# TeamG_PCB.net
KiCad netlist of a schematic drawn in EAGLE
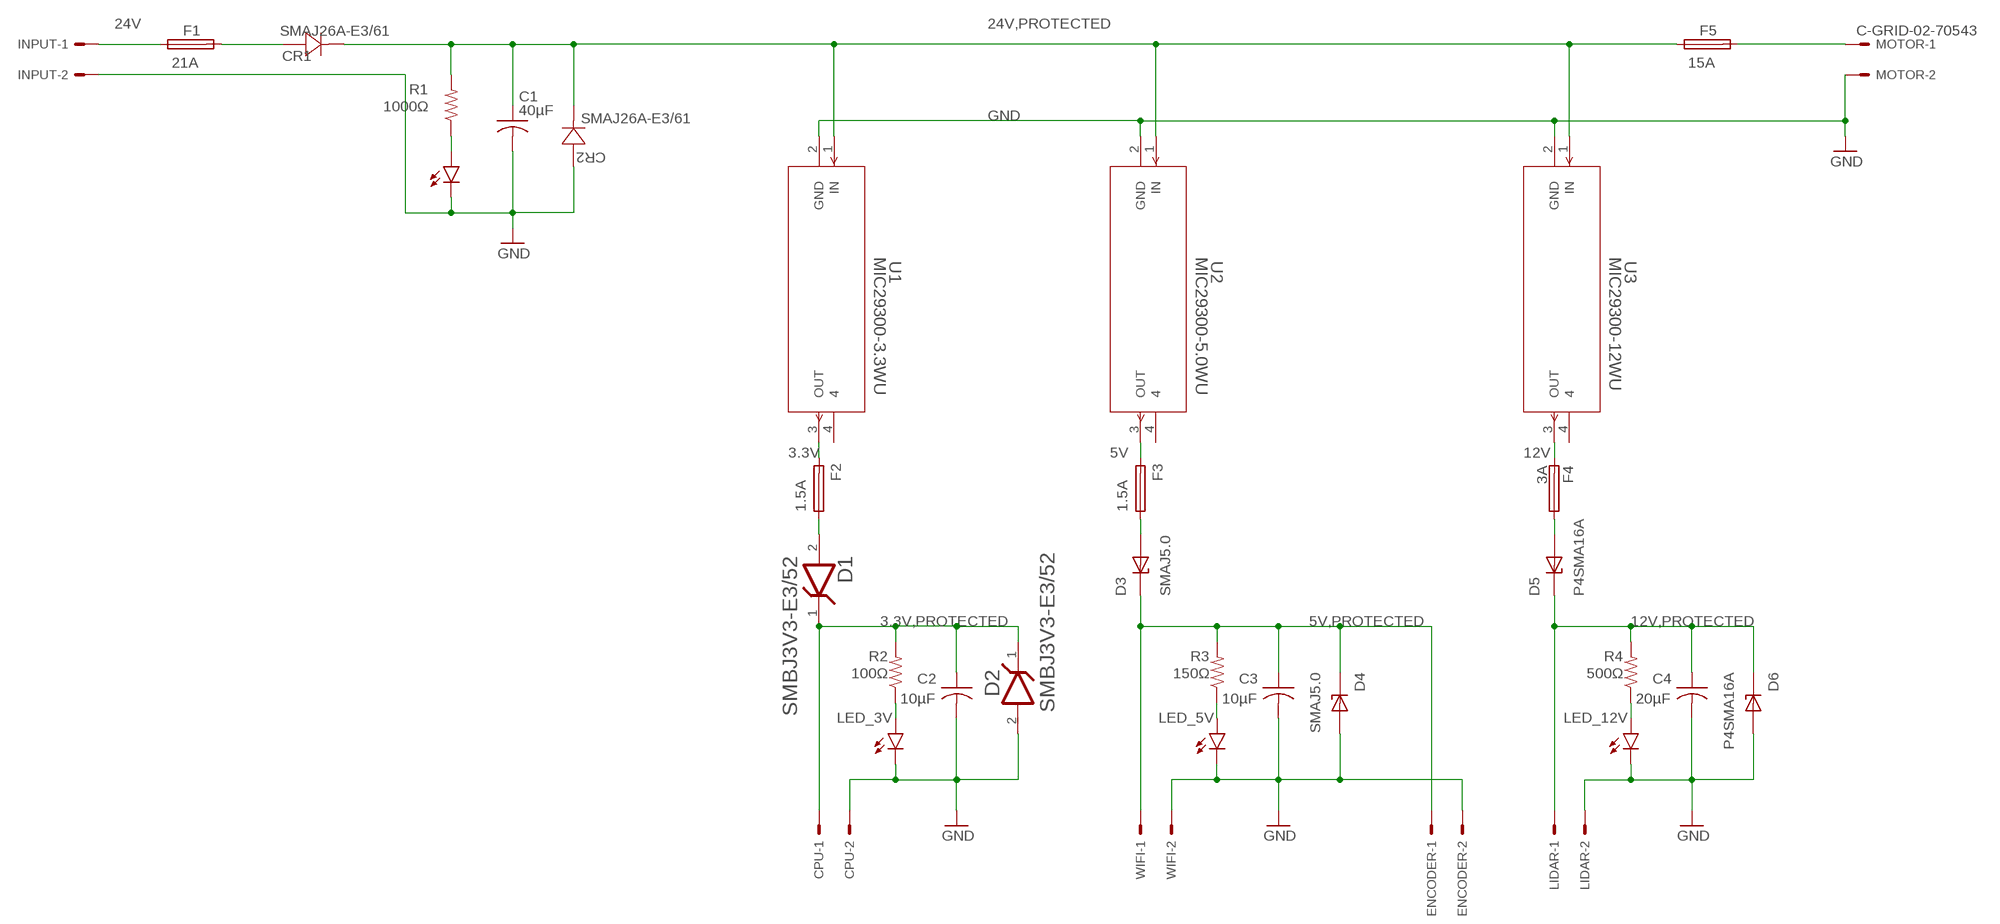
[diagram p0: schematic, sheet 1]

(export (version "E")
  (design (tool "Eeschema 10.0.6"))
  (components
    (comp (ref "24VLED")
      (value "0")
      (footprint "eagle-import:1206")
      (libsource (lib "eagle-import") (part "LEDSMT1206"))
    )
    (comp (ref "C1")
      (value "40µF")
      (footprint "eagle-import:C1210")
      (libsource (lib "eagle-import") (part "C-USC1210"))
    )
    (comp (ref "C2")
      (value "10µF")
      (footprint "eagle-import:C1210")
      (libsource (lib "eagle-import") (part "C-USC1210"))
    )
    (comp (ref "C3")
      (value "10µF")
      (footprint "eagle-import:C1210")
      (libsource (lib "eagle-import") (part "C-USC1210"))
    )
    (comp (ref "C4")
      (value "20µF")
      (footprint "eagle-import:C1210")
      (libsource (lib "eagle-import") (part "C-USC1210"))
    )
    (comp (ref "CPU")
      (value "C-GRID-02-70543")
      (footprint "eagle-import:70543-02")
      (fields (field (name "MF") "MOLEX"))
      (libsource (lib "eagle-import") (part "C-GRID-02-70543"))
    )
    (comp (ref "CR1")
      (value "SMAJ26A-E3/61")
      (footprint "eagle-import:DIODE_DO-214AC")
      (fields (field (name "COPYRIGHT") "Copyright (C) 2022 Ultra Librarian. All rights reserved."))
      (libsource (lib "eagle-import") (part "SMAJ26A-E3/61"))
    )
    (comp (ref "CR2")
      (value "SMAJ26A-E3/61")
      (footprint "eagle-import:DIODE_DO-214AC")
      (fields (field (name "COPYRIGHT") "Copyright (C) 2022 Ultra Librarian. All rights reserved."))
      (libsource (lib "eagle-import") (part "SMAJ26A-E3/61"))
    )
    (comp (ref "D1")
      (value "VISHAY_SMBJ3V3-E3-52VISHAY_SMBJ3V3-E3-52_0_0")
      (footprint "eagle-import:VISHAY_SMBJ3V3-E3-52_0")
      (fields
        (field (name "DIGIKEY_PART_NUMBER") "SMBJ3V3-E3/52GICT-ND")
        (field (name "MF") "Vishay")
        (field (name "MOUSER_PART_NUMBER") "625-SMBJ3V3-E3")
      )
      (libsource (lib "eagle-import") (part "VISHAY_SMBJ3V3-E3-52VISHAY_SMBJ3V3-E3-52_0_0"))
    )
    (comp (ref "D2")
      (value "VISHAY_SMBJ3V3-E3-52VISHAY_SMBJ3V3-E3-52_0_0")
      (footprint "eagle-import:VISHAY_SMBJ3V3-E3-52_0")
      (fields
        (field (name "DIGIKEY_PART_NUMBER") "SMBJ3V3-E3/52GICT-ND")
        (field (name "MF") "Vishay")
        (field (name "MOUSER_PART_NUMBER") "625-SMBJ3V3-E3")
      )
      (libsource (lib "eagle-import") (part "VISHAY_SMBJ3V3-E3-52VISHAY_SMBJ3V3-E3-52_0_0"))
    )
    (comp (ref "D3")
      (value "SMAJ5.0")
      (footprint "eagle-import:DIOM4325X250N")
      (fields (field (name "MF") "Taiwan Semiconductor"))
      (libsource (lib "eagle-import") (part "SMAJ5.0"))
    )
    (comp (ref "D4")
      (value "SMAJ5.0")
      (footprint "eagle-import:DIOM4325X250N")
      (fields (field (name "MF") "Taiwan Semiconductor"))
      (libsource (lib "eagle-import") (part "SMAJ5.0"))
    )
    (comp (ref "D5")
      (value "P4SMA16A")
      (footprint "eagle-import:DIOM4325X250N")
      (fields (field (name "MF") "Taiwan Semiconductor"))
      (libsource (lib "eagle-import") (part "P4SMA16A"))
    )
    (comp (ref "D6")
      (value "P4SMA16A")
      (footprint "eagle-import:DIOM4325X250N")
      (fields (field (name "MF") "Taiwan Semiconductor"))
      (libsource (lib "eagle-import") (part "P4SMA16A"))
    )
    (comp (ref "ENCODER")
      (value "C-GRID-02-70543")
      (footprint "eagle-import:70543-02")
      (fields (field (name "MF") "MOLEX"))
      (libsource (lib "eagle-import") (part "C-GRID-02-70543"))
    )
    (comp (ref "F1")
      (value "21A")
      (footprint "eagle-import:TE5")
      (libsource (lib "eagle-import") (part "TE5"))
    )
    (comp (ref "F2")
      (value "1.5A")
      (footprint "eagle-import:TE5")
      (libsource (lib "eagle-import") (part "TE5"))
    )
    (comp (ref "F3")
      (value "1.5A")
      (footprint "eagle-import:TE5")
      (libsource (lib "eagle-import") (part "TE5"))
    )
    (comp (ref "F4")
      (value "3A")
      (footprint "eagle-import:TE5")
      (libsource (lib "eagle-import") (part "TE5"))
    )
    (comp (ref "F5")
      (value "15A")
      (footprint "eagle-import:TE5")
      (libsource (lib "eagle-import") (part "TE5"))
    )
    (comp (ref "INPUT")
      (value "5566-2")
      (footprint "eagle-import:5566-2")
      (libsource (lib "eagle-import") (part "5566-2"))
    )
    (comp (ref "LED_3V")
      (value "0")
      (footprint "eagle-import:1206")
      (libsource (lib "eagle-import") (part "LEDSMT1206"))
    )
    (comp (ref "LED_5V")
      (value "0")
      (footprint "eagle-import:1206")
      (libsource (lib "eagle-import") (part "LEDSMT1206"))
    )
    (comp (ref "LED_12V")
      (value "0")
      (footprint "eagle-import:1206")
      (libsource (lib "eagle-import") (part "LEDSMT1206"))
    )
    (comp (ref "LIDAR")
      (value "C-GRID-02-70543")
      (footprint "eagle-import:70543-02")
      (fields (field (name "MF") "MOLEX"))
      (libsource (lib "eagle-import") (part "C-GRID-02-70543"))
    )
    (comp (ref "MOTOR")
      (value "C-GRID-02-70543")
      (footprint "eagle-import:70543-02")
      (fields (field (name "MF") "MOLEX"))
      (libsource (lib "eagle-import") (part "C-GRID-02-70543"))
    )
    (comp (ref "R1")
      (value "1000Ω")
      (footprint "eagle-import:R1206")
      (libsource (lib "eagle-import") (part "R-US_R1206"))
    )
    (comp (ref "R2")
      (value "100Ω")
      (footprint "eagle-import:R1206")
      (libsource (lib "eagle-import") (part "R-US_R1206"))
    )
    (comp (ref "R3")
      (value "150Ω")
      (footprint "eagle-import:R1206")
      (libsource (lib "eagle-import") (part "R-US_R1206"))
    )
    (comp (ref "R4")
      (value "500Ω")
      (footprint "eagle-import:R1206")
      (libsource (lib "eagle-import") (part "R-US_R1206"))
    )
    (comp (ref "U1")
      (value "MIC29300-3.3WU")
      (footprint "eagle-import:TO-263-3_MCL")
      (fields (field (name "COPYRIGHT") "Copyright (C) 2022 Ultra Librarian. All rights reserved."))
      (libsource (lib "eagle-import") (part "MIC29300-3.3WU"))
    )
    (comp (ref "U2")
      (value "MIC29300-5.0WU")
      (footprint "eagle-import:TO-263-3_MCL")
      (fields (field (name "COPYRIGHT") "Copyright (C) 2022 Ultra Librarian. All rights reserved."))
      (libsource (lib "eagle-import") (part "MIC29300-5.0WU"))
    )
    (comp (ref "U3")
      (value "MIC29300-12WU")
      (footprint "eagle-import:TO-263-3_MCL")
      (fields (field (name "COPYRIGHT") "Copyright (C) 2022 Ultra Librarian. All rights reserved."))
      (libsource (lib "eagle-import") (part "MIC29300-12WU"))
    )
    (comp (ref "WIFI")
      (value "C-GRID-02-70543")
      (footprint "eagle-import:70543-02")
      (fields (field (name "MF") "MOLEX"))
      (libsource (lib "eagle-import") (part "C-GRID-02-70543"))
    )
  )
  (nets
    (net (code "1") (name "/3.3V") (class "Default")
      (node (ref "F2") (pin "2") (pinfunction "2_2") (pintype "passive"))
      (node (ref "U1") (pin "3") (pinfunction "OUT_3") (pintype "output"))
    )
    (net (code "2") (name "/3.3V,PROTECTED") (class "Default")
      (node (ref "C2") (pin "1") (pinfunction "1_1") (pintype "passive"))
      (node (ref "CPU") (pin "1") (pinfunction "S_1") (pintype "passive"))
      (node (ref "D1") (pin "1") (pinfunction "CATHODE_1") (pintype "passive"))
      (node (ref "D2") (pin "1") (pinfunction "CATHODE_1") (pintype "passive"))
      (node (ref "R2") (pin "2") (pinfunction "2_2") (pintype "passive"))
    )
    (net (code "3") (name "/5V") (class "Default")
      (node (ref "F3") (pin "2") (pinfunction "2_2") (pintype "passive"))
      (node (ref "U2") (pin "3") (pinfunction "OUT_3") (pintype "output"))
    )
    (net (code "4") (name "/5V,PROTECTED") (class "Default")
      (node (ref "C3") (pin "1") (pinfunction "1_1") (pintype "passive"))
      (node (ref "D3") (pin "C") (pinfunction "C_C") (pintype "passive"))
      (node (ref "D4") (pin "C") (pinfunction "C_C") (pintype "passive"))
      (node (ref "ENCODER") (pin "1") (pinfunction "S_1") (pintype "passive"))
      (node (ref "R3") (pin "2") (pinfunction "2_2") (pintype "passive"))
      (node (ref "WIFI") (pin "1") (pinfunction "S_1") (pintype "passive"))
    )
    (net (code "5") (name "/12V") (class "Default")
      (node (ref "F4") (pin "2") (pinfunction "2_2") (pintype "passive"))
      (node (ref "U3") (pin "3") (pinfunction "OUT_3") (pintype "output"))
    )
    (net (code "6") (name "/12V,PROTECTED") (class "Default")
      (node (ref "C4") (pin "1") (pinfunction "1_1") (pintype "passive"))
      (node (ref "D5") (pin "C") (pinfunction "C_C") (pintype "passive"))
      (node (ref "D6") (pin "C") (pinfunction "C_C") (pintype "passive"))
      (node (ref "LIDAR") (pin "1") (pinfunction "S_1") (pintype "passive"))
      (node (ref "R4") (pin "2") (pinfunction "2_2") (pintype "passive"))
    )
    (net (code "7") (name "/24V") (class "Default")
      (node (ref "F1") (pin "1") (pinfunction "1_1") (pintype "passive"))
      (node (ref "INPUT") (pin "1") (pinfunction "S_1") (pintype "passive"))
    )
    (net (code "8") (name "/24V,PROTECTED") (class "Default")
      (node (ref "C1") (pin "1") (pinfunction "1_1") (pintype "passive"))
      (node (ref "CR1") (pin "1") (pinfunction "1_1") (pintype "passive"))
      (node (ref "CR2") (pin "1") (pinfunction "1_1") (pintype "passive"))
      (node (ref "F5") (pin "1") (pinfunction "1_1") (pintype "passive"))
      (node (ref "R1") (pin "2") (pinfunction "2_2") (pintype "passive"))
      (node (ref "U1") (pin "1") (pinfunction "IN_1") (pintype "input"))
      (node (ref "U2") (pin "1") (pinfunction "IN_1") (pintype "input"))
      (node (ref "U3") (pin "1") (pinfunction "IN_1") (pintype "input"))
    )
    (net (code "9") (name "GND") (class "Default")
      (node (ref "24VLED") (pin "C") (pinfunction "C_C") (pintype "passive"))
      (node (ref "C1") (pin "2") (pinfunction "2_2") (pintype "passive"))
      (node (ref "C2") (pin "2") (pinfunction "2_2") (pintype "passive"))
      (node (ref "C3") (pin "2") (pinfunction "2_2") (pintype "passive"))
      (node (ref "C4") (pin "2") (pinfunction "2_2") (pintype "passive"))
      (node (ref "CPU") (pin "2") (pinfunction "S_2") (pintype "passive"))
      (node (ref "CR2") (pin "2") (pinfunction "2_2") (pintype "passive"))
      (node (ref "D2") (pin "2") (pinfunction "ANODE_2") (pintype "passive"))
      (node (ref "D4") (pin "A") (pinfunction "A_A") (pintype "passive"))
      (node (ref "D6") (pin "A") (pinfunction "A_A") (pintype "passive"))
      (node (ref "ENCODER") (pin "2") (pinfunction "S_2") (pintype "passive"))
      (node (ref "INPUT") (pin "2") (pinfunction "S_2") (pintype "passive"))
      (node (ref "LED_12V") (pin "C") (pinfunction "C_C") (pintype "passive"))
      (node (ref "LED_3V") (pin "C") (pinfunction "C_C") (pintype "passive"))
      (node (ref "LED_5V") (pin "C") (pinfunction "C_C") (pintype "passive"))
      (node (ref "LIDAR") (pin "2") (pinfunction "S_2") (pintype "passive"))
      (node (ref "MOTOR") (pin "2") (pinfunction "S_2") (pintype "passive"))
      (node (ref "U1") (pin "2") (pinfunction "GND_2") (pintype "power_in"))
      (node (ref "U2") (pin "2") (pinfunction "GND_2") (pintype "power_in"))
      (node (ref "U3") (pin "2") (pinfunction "GND_2") (pintype "power_in"))
      (node (ref "WIFI") (pin "2") (pinfunction "S_2") (pintype "passive"))
    )
    (net (code "10") (name "Net-(24VLED-PadA)") (class "Default")
      (node (ref "24VLED") (pin "A") (pinfunction "A_A") (pintype "passive"))
      (node (ref "R1") (pin "1") (pinfunction "1_1") (pintype "passive"))
    )
    (net (code "11") (name "Net-(CR1-Pad2)") (class "Default")
      (node (ref "CR1") (pin "2") (pinfunction "2_2") (pintype "passive"))
      (node (ref "F1") (pin "2") (pinfunction "2_2") (pintype "passive"))
    )
    (net (code "12") (name "Net-(D1-ANODE)") (class "Default")
      (node (ref "D1") (pin "2") (pinfunction "ANODE_2") (pintype "passive"))
      (node (ref "F2") (pin "1") (pinfunction "1_1") (pintype "passive"))
    )
    (net (code "13") (name "Net-(D3-PadA)") (class "Default")
      (node (ref "D3") (pin "A") (pinfunction "A_A") (pintype "passive"))
      (node (ref "F3") (pin "1") (pinfunction "1_1") (pintype "passive"))
    )
    (net (code "14") (name "Net-(D5-PadA)") (class "Default")
      (node (ref "D5") (pin "A") (pinfunction "A_A") (pintype "passive"))
      (node (ref "F4") (pin "1") (pinfunction "1_1") (pintype "passive"))
    )
    (net (code "15") (name "Net-(LED_3V-PadA)") (class "Default")
      (node (ref "LED_3V") (pin "A") (pinfunction "A_A") (pintype "passive"))
      (node (ref "R2") (pin "1") (pinfunction "1_1") (pintype "passive"))
    )
    (net (code "16") (name "Net-(LED_5V-PadA)") (class "Default")
      (node (ref "LED_5V") (pin "A") (pinfunction "A_A") (pintype "passive"))
      (node (ref "R3") (pin "1") (pinfunction "1_1") (pintype "passive"))
    )
    (net (code "17") (name "Net-(LED_12V-PadA)") (class "Default")
      (node (ref "LED_12V") (pin "A") (pinfunction "A_A") (pintype "passive"))
      (node (ref "R4") (pin "1") (pinfunction "1_1") (pintype "passive"))
    )
    (net (code "18") (name "Net-(MOTORA-S)") (class "Default")
      (node (ref "F5") (pin "2") (pinfunction "2_2") (pintype "passive"))
      (node (ref "MOTOR") (pin "1") (pinfunction "S_1") (pintype "passive"))
    )
    (net (code "19") (name "unconnected-(U1-Pad4)") (class "Default")
      (node (ref "U1") (pin "4") (pinfunction "4_4") (pintype "passive"))
    )
    (net (code "20") (name "unconnected-(U2-Pad4)") (class "Default")
      (node (ref "U2") (pin "4") (pinfunction "4_4") (pintype "passive"))
    )
    (net (code "21") (name "unconnected-(U3-Pad4)") (class "Default")
      (node (ref "U3") (pin "4") (pinfunction "4_4") (pintype "passive"))
    )
  )
)
